# AS3364_quad_VCA_0402_DIL-inv_v1_0.net
KiCad netlist of a schematic drawn in EAGLE
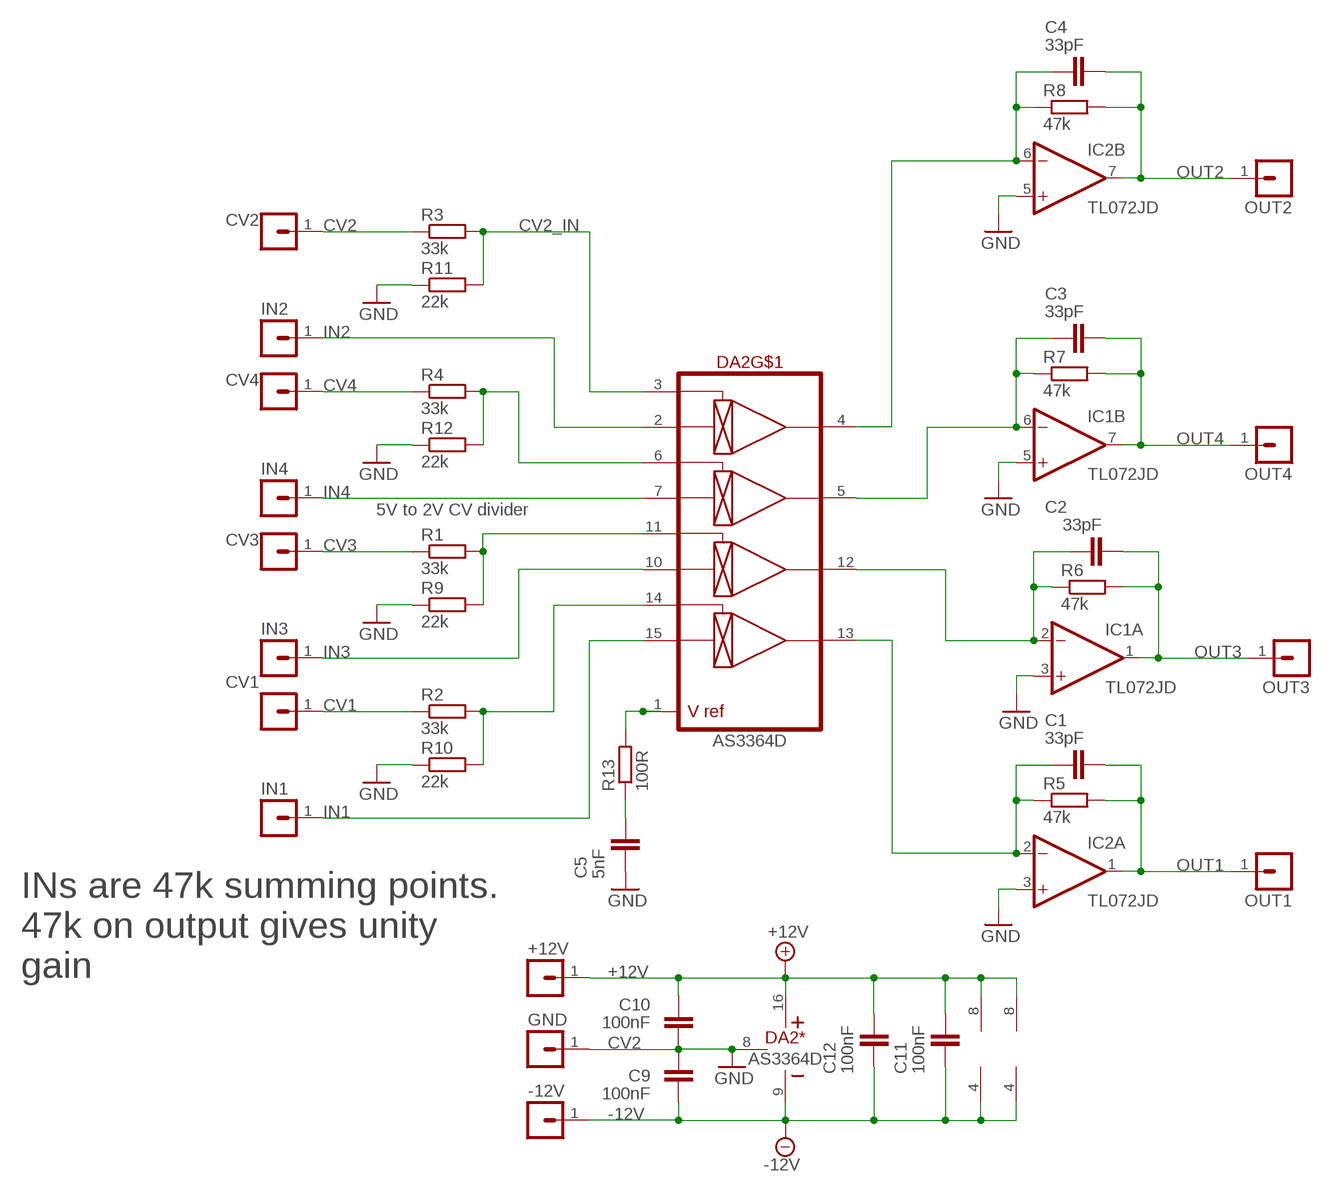
[diagram p0: schematic, sheet 1]

(export (version "E")
  (design (tool "Eeschema 10.0.6"))
  (components
    (comp (ref "+12V")
      (value "MA01-1JP")
      (footprint "eagle-import:SIP-PIN01-1J")
      (libsource (lib "eagle-import") (part "MA01-1JP"))
    )
    (comp (ref "-12V")
      (value "MA01-1JP")
      (footprint "eagle-import:SIP-PIN01-1J")
      (libsource (lib "eagle-import") (part "MA01-1JP"))
    )
    (comp (ref "C1")
      (value "33pF")
      (footprint "eagle-import:C0402")
      (libsource (lib "eagle-import") (part "C-EUC0402"))
    )
    (comp (ref "C2")
      (value "33pF")
      (footprint "eagle-import:C0402")
      (libsource (lib "eagle-import") (part "C-EUC0402"))
    )
    (comp (ref "C3")
      (value "33pF")
      (footprint "eagle-import:C0402")
      (libsource (lib "eagle-import") (part "C-EUC0402"))
    )
    (comp (ref "C4")
      (value "33pF")
      (footprint "eagle-import:C0402")
      (libsource (lib "eagle-import") (part "C-EUC0402"))
    )
    (comp (ref "C5")
      (value "5nF")
      (footprint "eagle-import:C0402")
      (libsource (lib "eagle-import") (part "C-EUC0402"))
    )
    (comp (ref "C9")
      (value "100nF")
      (footprint "eagle-import:C0402")
      (libsource (lib "eagle-import") (part "C-EUC0402"))
    )
    (comp (ref "C10")
      (value "100nF")
      (footprint "eagle-import:C0402")
      (libsource (lib "eagle-import") (part "C-EUC0402"))
    )
    (comp (ref "C11")
      (value "100nF")
      (footprint "eagle-import:C0402")
      (libsource (lib "eagle-import") (part "C-EUC0402"))
    )
    (comp (ref "C12")
      (value "100nF")
      (footprint "eagle-import:C0402")
      (libsource (lib "eagle-import") (part "C-EUC0402"))
    )
    (comp (ref "CV1")
      (value "MA01-1JP")
      (footprint "eagle-import:SIP-PIN01-1J")
      (libsource (lib "eagle-import") (part "MA01-1JP"))
    )
    (comp (ref "CV2")
      (value "MA01-1JP")
      (footprint "eagle-import:SIP-PIN01-1J")
      (libsource (lib "eagle-import") (part "MA01-1JP"))
    )
    (comp (ref "CV3")
      (value "MA01-1JP")
      (footprint "eagle-import:SIP-PIN01-1J")
      (libsource (lib "eagle-import") (part "MA01-1JP"))
    )
    (comp (ref "CV4")
      (value "MA01-1JP")
      (footprint "eagle-import:SIP-PIN01-1J")
      (libsource (lib "eagle-import") (part "MA01-1JP"))
    )
    (comp (ref "DA2")
      (value "AS3364D")
      (footprint "eagle-import:DIL16J")
      (libsource (lib "eagle-import") (part "AS3364D"))
    )
    (comp (ref "GND")
      (value "MA01-1JP")
      (footprint "eagle-import:SIP-PIN01-1J")
      (libsource (lib "eagle-import") (part "MA01-1JP"))
    )
    (comp (ref "IC1")
      (value "TL072JD")
      (footprint "eagle-import:SO08J")
      (libsource (lib "eagle-import") (part "TL072JD"))
    )
    (comp (ref "IC2")
      (value "TL072JD")
      (footprint "eagle-import:SO08J")
      (libsource (lib "eagle-import") (part "TL072JD"))
    )
    (comp (ref "IN1")
      (value "MA01-1JP")
      (footprint "eagle-import:SIP-PIN01-1J")
      (libsource (lib "eagle-import") (part "MA01-1JP"))
    )
    (comp (ref "IN2")
      (value "MA01-1JP")
      (footprint "eagle-import:SIP-PIN01-1J")
      (libsource (lib "eagle-import") (part "MA01-1JP"))
    )
    (comp (ref "IN3")
      (value "MA01-1JP")
      (footprint "eagle-import:SIP-PIN01-1J")
      (libsource (lib "eagle-import") (part "MA01-1JP"))
    )
    (comp (ref "IN4")
      (value "MA01-1JP")
      (footprint "eagle-import:SIP-PIN01-1J")
      (libsource (lib "eagle-import") (part "MA01-1JP"))
    )
    (comp (ref "OUT1")
      (value "MA01-1JP")
      (footprint "eagle-import:SIP-PIN01-1J")
      (libsource (lib "eagle-import") (part "MA01-1JP"))
    )
    (comp (ref "OUT2")
      (value "MA01-1JP")
      (footprint "eagle-import:SIP-PIN01-1J")
      (libsource (lib "eagle-import") (part "MA01-1JP"))
    )
    (comp (ref "OUT3")
      (value "MA01-1JP")
      (footprint "eagle-import:SIP-PIN01-1J")
      (libsource (lib "eagle-import") (part "MA01-1JP"))
    )
    (comp (ref "OUT4")
      (value "MA01-1JP")
      (footprint "eagle-import:SIP-PIN01-1J")
      (libsource (lib "eagle-import") (part "MA01-1JP"))
    )
    (comp (ref "R1")
      (value "33k")
      (footprint "eagle-import:R0402")
      (libsource (lib "eagle-import") (part "R-EU_R0402"))
    )
    (comp (ref "R2")
      (value "33k")
      (footprint "eagle-import:R0402")
      (libsource (lib "eagle-import") (part "R-EU_R0402"))
    )
    (comp (ref "R3")
      (value "33k")
      (footprint "eagle-import:R0402")
      (libsource (lib "eagle-import") (part "R-EU_R0402"))
    )
    (comp (ref "R4")
      (value "33k")
      (footprint "eagle-import:R0402")
      (libsource (lib "eagle-import") (part "R-EU_R0402"))
    )
    (comp (ref "R5")
      (value "47k")
      (footprint "eagle-import:R0402")
      (libsource (lib "eagle-import") (part "R-EU_R0402"))
    )
    (comp (ref "R6")
      (value "47k")
      (footprint "eagle-import:R0402")
      (libsource (lib "eagle-import") (part "R-EU_R0402"))
    )
    (comp (ref "R7")
      (value "47k")
      (footprint "eagle-import:R0402")
      (libsource (lib "eagle-import") (part "R-EU_R0402"))
    )
    (comp (ref "R8")
      (value "47k")
      (footprint "eagle-import:R0402")
      (libsource (lib "eagle-import") (part "R-EU_R0402"))
    )
    (comp (ref "R9")
      (value "22k")
      (footprint "eagle-import:R0402")
      (libsource (lib "eagle-import") (part "R-EU_R0402"))
    )
    (comp (ref "R10")
      (value "22k")
      (footprint "eagle-import:R0402")
      (libsource (lib "eagle-import") (part "R-EU_R0402"))
    )
    (comp (ref "R11")
      (value "22k")
      (footprint "eagle-import:R0402")
      (libsource (lib "eagle-import") (part "R-EU_R0402"))
    )
    (comp (ref "R12")
      (value "22k")
      (footprint "eagle-import:R0402")
      (libsource (lib "eagle-import") (part "R-EU_R0402"))
    )
    (comp (ref "R13")
      (value "100R")
      (footprint "eagle-import:R0402")
      (libsource (lib "eagle-import") (part "R-EU_R0402"))
    )
  )
  (nets
    (net (code "1") (name "+12V") (class "Default")
      (node (ref "+12V") (pin "1") (pinfunction "1_1") (pintype "passive"))
      (node (ref "C10") (pin "2") (pinfunction "2_2") (pintype "passive"))
      (node (ref "C11") (pin "2") (pinfunction "2_2") (pintype "passive"))
      (node (ref "C12") (pin "2") (pinfunction "2_2") (pintype "passive"))
      (node (ref "DA2") (pin "16") (pinfunction "V+_16") (pintype "power_in"))
      (node (ref "IC1") (pin "8") (pinfunction "V+_8") (pintype "power_in"))
      (node (ref "IC2") (pin "8") (pinfunction "V+_8") (pintype "power_in"))
    )
    (net (code "2") (name "-12V") (class "Default")
      (node (ref "-12V") (pin "1") (pinfunction "1_1") (pintype "passive"))
      (node (ref "C11") (pin "1") (pinfunction "1_1") (pintype "passive"))
      (node (ref "C12") (pin "1") (pinfunction "1_1") (pintype "passive"))
      (node (ref "C9") (pin "1") (pinfunction "1_1") (pintype "passive"))
      (node (ref "DA2") (pin "9") (pinfunction "V-_9") (pintype "power_in"))
      (node (ref "IC1") (pin "4") (pinfunction "V-_4") (pintype "power_in"))
      (node (ref "IC2") (pin "4") (pinfunction "V-_4") (pintype "power_in"))
    )
    (net (code "3") (name "/CV1") (class "Default")
      (node (ref "CV1") (pin "1") (pinfunction "1_1") (pintype "passive"))
      (node (ref "R2") (pin "1") (pinfunction "1_1") (pintype "passive"))
    )
    (net (code "4") (name "/CV2") (class "Default")
      (node (ref "CV2") (pin "1") (pinfunction "1_1") (pintype "passive"))
      (node (ref "R3") (pin "1") (pinfunction "1_1") (pintype "passive"))
    )
    (net (code "5") (name "/CV2_IN") (class "Default")
      (node (ref "DA2") (pin "3") (pinfunction "CV1_3") (pintype "input"))
      (node (ref "R11") (pin "2") (pinfunction "2_2") (pintype "passive"))
      (node (ref "R3") (pin "2") (pinfunction "2_2") (pintype "passive"))
    )
    (net (code "6") (name "/CV3") (class "Default")
      (node (ref "CV3") (pin "1") (pinfunction "1_1") (pintype "passive"))
      (node (ref "R1") (pin "1") (pinfunction "1_1") (pintype "passive"))
    )
    (net (code "7") (name "/CV4") (class "Default")
      (node (ref "CV4") (pin "1") (pinfunction "1_1") (pintype "passive"))
      (node (ref "R4") (pin "1") (pinfunction "1_1") (pintype "passive"))
    )
    (net (code "8") (name "/IN1") (class "Default")
      (node (ref "DA2") (pin "15") (pinfunction "IN4_15") (pintype "input"))
      (node (ref "IN1") (pin "1") (pinfunction "1_1") (pintype "passive"))
    )
    (net (code "9") (name "/IN2") (class "Default")
      (node (ref "DA2") (pin "2") (pinfunction "IN1_2") (pintype "input"))
      (node (ref "IN2") (pin "1") (pinfunction "1_1") (pintype "passive"))
    )
    (net (code "10") (name "/IN3") (class "Default")
      (node (ref "DA2") (pin "10") (pinfunction "IN3_10") (pintype "input"))
      (node (ref "IN3") (pin "1") (pinfunction "1_1") (pintype "passive"))
    )
    (net (code "11") (name "/IN4") (class "Default")
      (node (ref "DA2") (pin "7") (pinfunction "IN2_7") (pintype "input"))
      (node (ref "IN4") (pin "1") (pinfunction "1_1") (pintype "passive"))
    )
    (net (code "12") (name "/OUT1") (class "Default")
      (node (ref "C1") (pin "2") (pinfunction "2_2") (pintype "passive"))
      (node (ref "IC2") (pin "1") (pinfunction "OUT_1") (pintype "output"))
      (node (ref "OUT1") (pin "1") (pinfunction "1_1") (pintype "passive"))
      (node (ref "R5") (pin "2") (pinfunction "2_2") (pintype "passive"))
    )
    (net (code "13") (name "/OUT2") (class "Default")
      (node (ref "C4") (pin "2") (pinfunction "2_2") (pintype "passive"))
      (node (ref "IC2") (pin "7") (pinfunction "OUT_7") (pintype "output"))
      (node (ref "OUT2") (pin "1") (pinfunction "1_1") (pintype "passive"))
      (node (ref "R8") (pin "2") (pinfunction "2_2") (pintype "passive"))
    )
    (net (code "14") (name "/OUT3") (class "Default")
      (node (ref "C2") (pin "2") (pinfunction "2_2") (pintype "passive"))
      (node (ref "IC1") (pin "1") (pinfunction "OUT_1") (pintype "output"))
      (node (ref "OUT3") (pin "1") (pinfunction "1_1") (pintype "passive"))
      (node (ref "R6") (pin "2") (pinfunction "2_2") (pintype "passive"))
    )
    (net (code "15") (name "/OUT4") (class "Default")
      (node (ref "C3") (pin "2") (pinfunction "2_2") (pintype "passive"))
      (node (ref "IC1") (pin "7") (pinfunction "OUT_7") (pintype "output"))
      (node (ref "OUT4") (pin "1") (pinfunction "1_1") (pintype "passive"))
      (node (ref "R7") (pin "2") (pinfunction "2_2") (pintype "passive"))
    )
    (net (code "16") (name "GND") (class "Default")
      (node (ref "C10") (pin "1") (pinfunction "1_1") (pintype "passive"))
      (node (ref "C5") (pin "1") (pinfunction "1_1") (pintype "passive"))
      (node (ref "C9") (pin "2") (pinfunction "2_2") (pintype "passive"))
      (node (ref "DA2") (pin "8") (pinfunction "GND_8") (pintype "power_in"))
      (node (ref "GND") (pin "1") (pinfunction "1_1") (pintype "passive"))
      (node (ref "IC1") (pin "3") (pinfunction "+IN_3") (pintype "input"))
      (node (ref "IC1") (pin "5") (pinfunction "+IN_5") (pintype "input"))
      (node (ref "IC2") (pin "3") (pinfunction "+IN_3") (pintype "input"))
      (node (ref "IC2") (pin "5") (pinfunction "+IN_5") (pintype "input"))
      (node (ref "R10") (pin "1") (pinfunction "1_1") (pintype "passive"))
      (node (ref "R11") (pin "1") (pinfunction "1_1") (pintype "passive"))
      (node (ref "R12") (pin "1") (pinfunction "1_1") (pintype "passive"))
      (node (ref "R9") (pin "1") (pinfunction "1_1") (pintype "passive"))
    )
    (net (code "17") (name "Net-(C5-Pad2)") (class "Default")
      (node (ref "C5") (pin "2") (pinfunction "2_2") (pintype "passive"))
      (node (ref "R13") (pin "1") (pinfunction "1_1") (pintype "passive"))
    )
    (net (code "18") (name "Net-(DA2B-CV2)") (class "Default")
      (node (ref "DA2") (pin "6") (pinfunction "CV2_6") (pintype "input"))
      (node (ref "R12") (pin "2") (pinfunction "2_2") (pintype "passive"))
      (node (ref "R4") (pin "2") (pinfunction "2_2") (pintype "passive"))
    )
    (net (code "19") (name "Net-(DA2B-CV3)") (class "Default")
      (node (ref "DA2") (pin "11") (pinfunction "CV3_11") (pintype "input"))
      (node (ref "R1") (pin "2") (pinfunction "2_2") (pintype "passive"))
      (node (ref "R9") (pin "2") (pinfunction "2_2") (pintype "passive"))
    )
    (net (code "20") (name "Net-(DA2B-CV4)") (class "Default")
      (node (ref "DA2") (pin "14") (pinfunction "CV4_14") (pintype "input"))
      (node (ref "R10") (pin "2") (pinfunction "2_2") (pintype "passive"))
      (node (ref "R2") (pin "2") (pinfunction "2_2") (pintype "passive"))
    )
    (net (code "21") (name "Net-(DA2B-OUT1)") (class "Default")
      (node (ref "C4") (pin "1") (pinfunction "1_1") (pintype "passive"))
      (node (ref "DA2") (pin "4") (pinfunction "OUT1_4") (pintype "output"))
      (node (ref "IC2") (pin "6") (pinfunction "-IN_6") (pintype "input"))
      (node (ref "R8") (pin "1") (pinfunction "1_1") (pintype "passive"))
    )
    (net (code "22") (name "Net-(DA2B-OUT2)") (class "Default")
      (node (ref "C3") (pin "1") (pinfunction "1_1") (pintype "passive"))
      (node (ref "DA2") (pin "5") (pinfunction "OUT2_5") (pintype "output"))
      (node (ref "IC1") (pin "6") (pinfunction "-IN_6") (pintype "input"))
      (node (ref "R7") (pin "1") (pinfunction "1_1") (pintype "passive"))
    )
    (net (code "23") (name "Net-(DA2B-OUT3)") (class "Default")
      (node (ref "C2") (pin "1") (pinfunction "1_1") (pintype "passive"))
      (node (ref "DA2") (pin "12") (pinfunction "OUT3_12") (pintype "output"))
      (node (ref "IC1") (pin "2") (pinfunction "-IN_2") (pintype "input"))
      (node (ref "R6") (pin "1") (pinfunction "1_1") (pintype "passive"))
    )
    (net (code "24") (name "Net-(DA2B-OUT4)") (class "Default")
      (node (ref "C1") (pin "1") (pinfunction "1_1") (pintype "passive"))
      (node (ref "DA2") (pin "13") (pinfunction "OUT4_13") (pintype "output"))
      (node (ref "IC2") (pin "2") (pinfunction "-IN_2") (pintype "input"))
      (node (ref "R5") (pin "1") (pinfunction "1_1") (pintype "passive"))
    )
    (net (code "25") (name "Net-(DA2B-VREF)") (class "Default")
      (node (ref "DA2") (pin "1") (pinfunction "VREF_1") (pintype "output"))
      (node (ref "R13") (pin "2") (pinfunction "2_2") (pintype "passive"))
    )
  )
)
